# 08_BB_Processor.net
KiCad netlist of a schematic drawn in Altium Designer
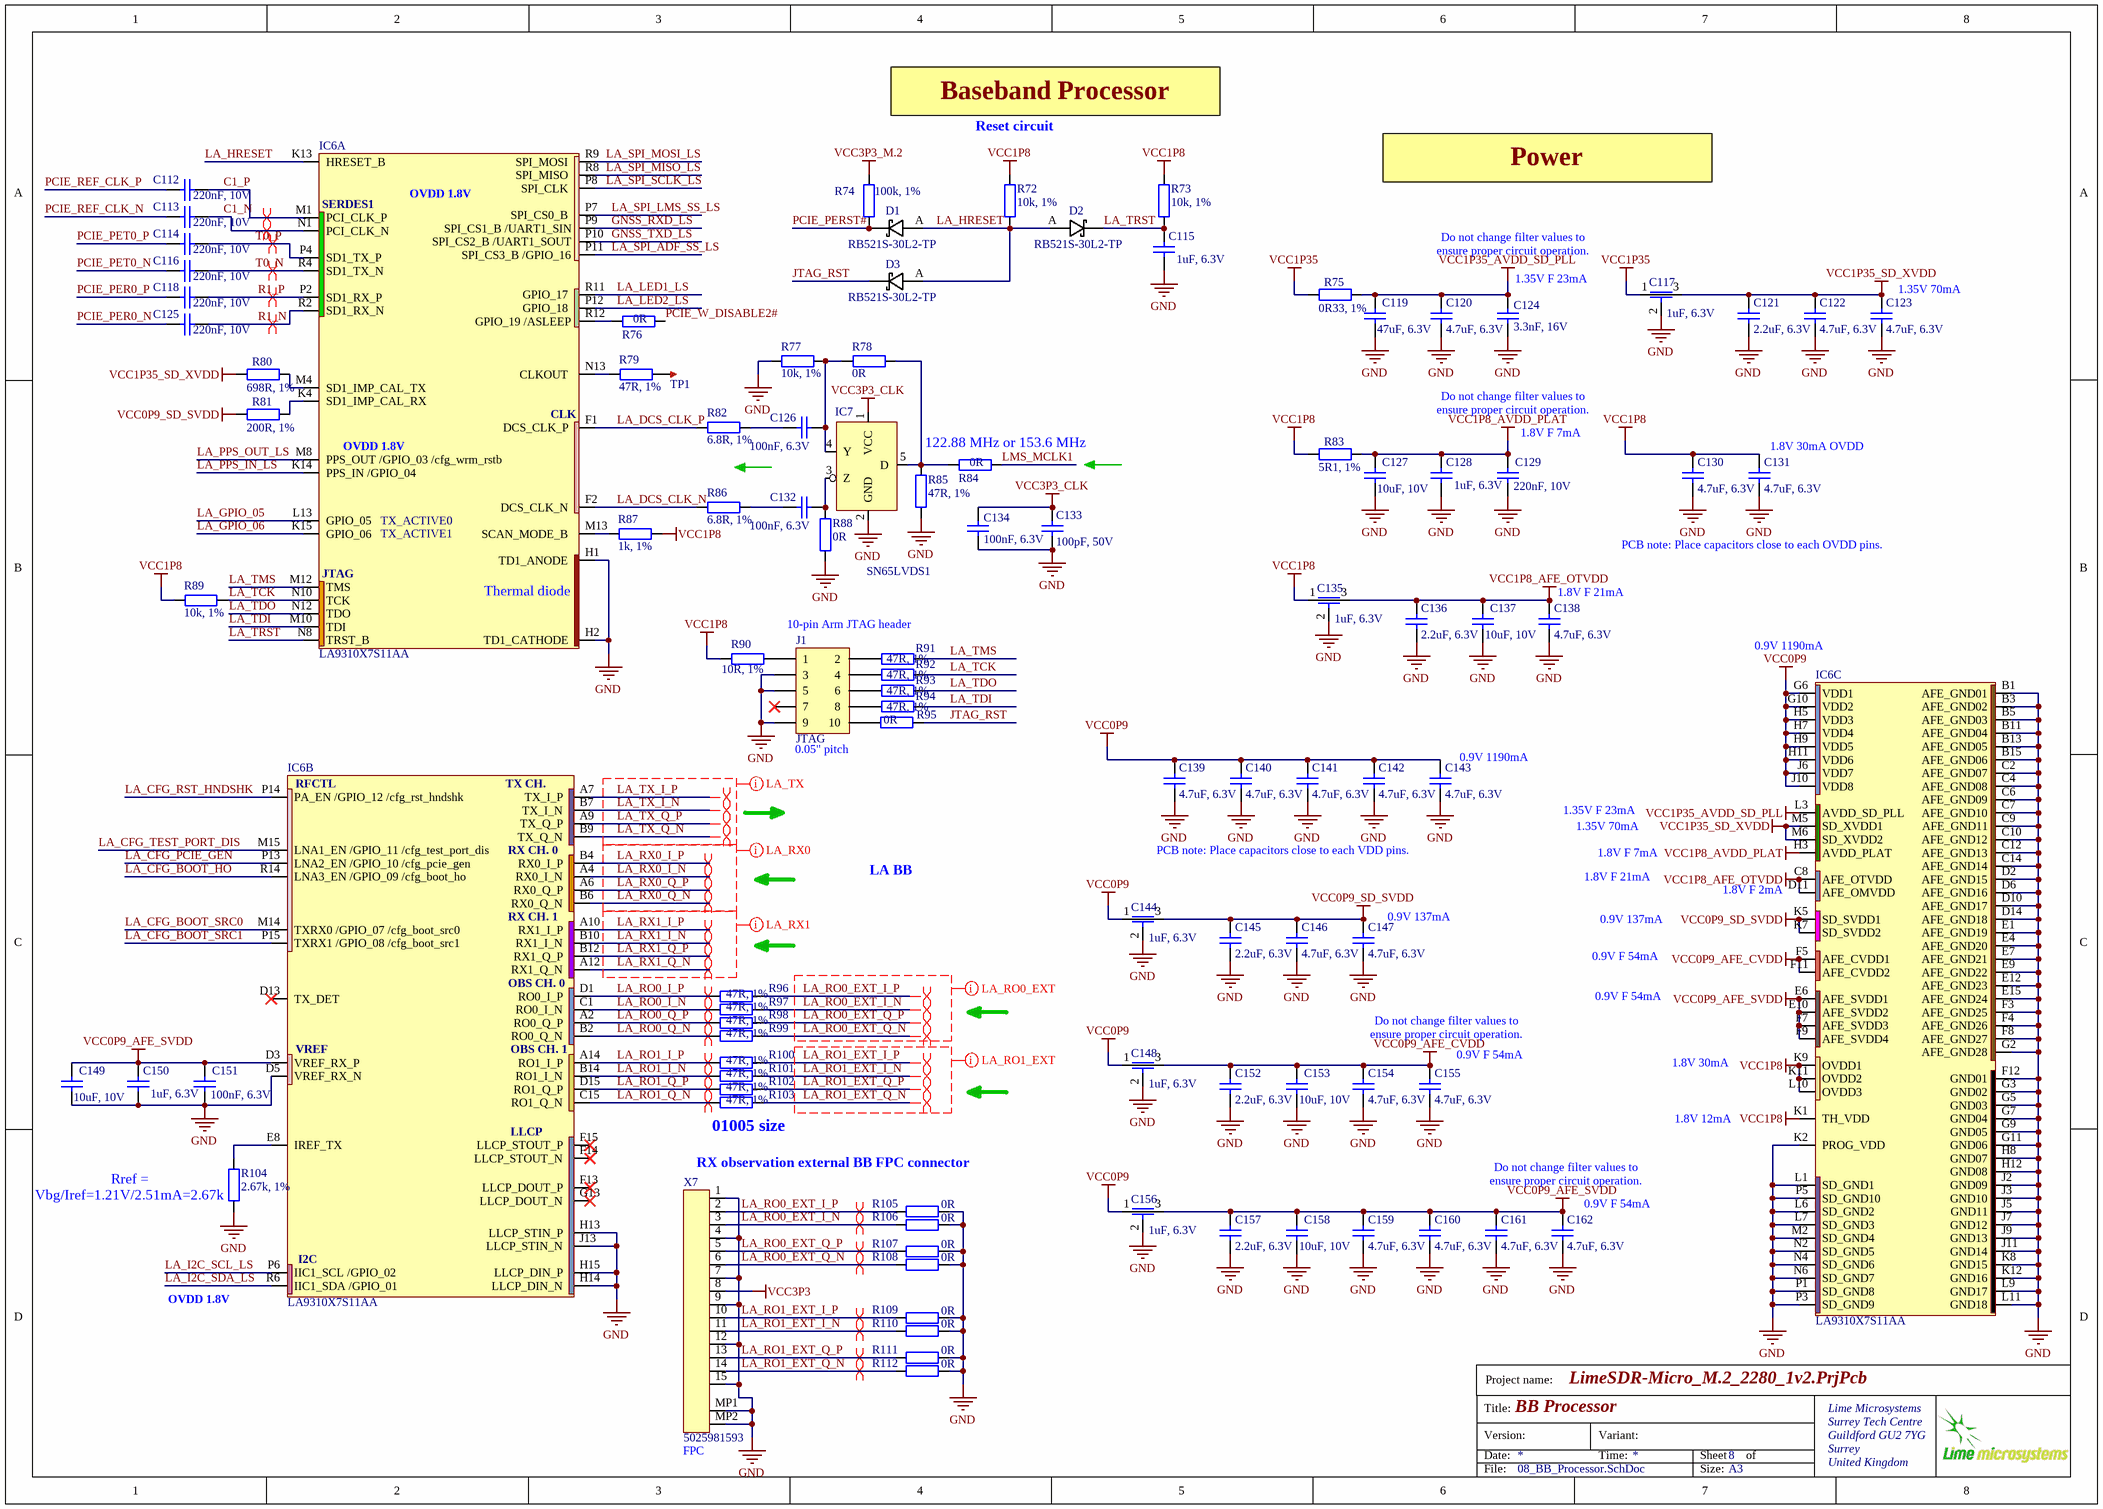
[diagram p0: 08_BB_Processor.SchDoc]

(export (version "E")
  (design (tool "Eeschema 10.0.6"))
  (components
    (comp (ref "C112")
      (value "220nF, 10V")
      (footprint "CAP0201")
      (fields
        (field (name "MANUFACTURER") "Murata")
        (field (name "TOLERANCE") "20%")
        (field (name "VOLTAGE") "10V")
      )
      (libsource (lib "LimeMicroAltiumLib_schLib") (part "Cap_0402"))
    )
    (comp (ref "C113")
      (value "220nF, 10V")
      (footprint "CAP0201")
      (fields
        (field (name "MANUFACTURER") "Murata")
        (field (name "TOLERANCE") "20%")
        (field (name "VOLTAGE") "10V")
      )
      (libsource (lib "LimeMicroAltiumLib_schLib") (part "Cap_0402"))
    )
    (comp (ref "C114")
      (value "220nF, 10V")
      (footprint "CAP0201")
      (fields
        (field (name "MANUFACTURER") "Murata")
        (field (name "TOLERANCE") "20%")
        (field (name "VOLTAGE") "10V")
      )
      (libsource (lib "LimeMicroAltiumLib_schLib") (part "Cap_0402"))
    )
    (comp (ref "C115")
      (value "1uF, 6.3V")
      (footprint "CAP0201")
      (fields (field (name "TOLERANCE") "±20%") (field (name "MANUFACTURER") "TDK Corporation"))
      (libsource (lib "LimeMicroAltiumLib_schLib") (part "Cap_0402"))
    )
    (comp (ref "C116")
      (value "220nF, 10V")
      (footprint "CAP0201")
      (fields
        (field (name "MANUFACTURER") "Murata")
        (field (name "TOLERANCE") "20%")
        (field (name "VOLTAGE") "10V")
      )
      (libsource (lib "LimeMicroAltiumLib_schLib") (part "Cap_0402"))
    )
    (comp (ref "C117")
      (value "1uF, 6.3V")
      (footprint "CAP0603_FEEDTHROUGH")
      (fields (field (name "MANUFACTURER") "TDK"))
      (libsource (lib "LimeMicroAltiumLib_schLib_r01") (part "Cap_feed_through"))
    )
    (comp (ref "C118")
      (value "220nF, 10V")
      (footprint "CAP0201")
      (fields
        (field (name "MANUFACTURER") "Murata")
        (field (name "TOLERANCE") "20%")
        (field (name "VOLTAGE") "10V")
      )
      (libsource (lib "LimeMicroAltiumLib_schLib") (part "Cap_0402"))
    )
    (comp (ref "C119")
      (value "47uF, 6.3V")
      (footprint "CAP0603")
      (fields (field (name "MANUFACTURER") "Murata") (field (name "TOLERANCE") "20%"))
      (libsource (lib "LimeFPGAboard_schLib") (part "Cap_0603"))
    )
    (comp (ref "C120")
      (value "4.7uF, 6.3V")
      (footprint "CAP0201")
      (fields (field (name "MANUFACTURER") "Murata") (field (name "TOLERANCE") "20%"))
      (libsource (lib "LimeMicroAltiumLib_schLib") (part "Cap_0402"))
    )
    (comp (ref "C121")
      (value "2.2uF, 6.3V")
      (footprint "CAP0201")
      (fields (field (name "MANUFACTURER") "Murata") (field (name "TOLERANCE") "20%"))
      (libsource (lib "LimeMicroAltiumLib_schLib") (part "Cap_0402"))
    )
    (comp (ref "C122")
      (value "4.7uF, 6.3V")
      (footprint "CAP0201")
      (fields (field (name "MANUFACTURER") "Murata") (field (name "TOLERANCE") "20%"))
      (libsource (lib "LimeMicroAltiumLib_schLib") (part "Cap_0402"))
    )
    (comp (ref "C123")
      (value "4.7uF, 6.3V")
      (footprint "CAP0201")
      (fields (field (name "MANUFACTURER") "Murata") (field (name "TOLERANCE") "20%"))
      (libsource (lib "LimeMicroAltiumLib_schLib") (part "Cap_0402"))
    )
    (comp (ref "C124")
      (value "3.3nF, 16V")
      (footprint "CAP0201")
      (fields (field (name "MANUFACTURER") "Murata"))
      (libsource (lib "LimeMicroAltiumLib_schLib") (part "Cap_0402"))
    )
    (comp (ref "C125")
      (value "220nF, 10V")
      (footprint "CAP0201")
      (fields
        (field (name "MANUFACTURER") "Murata")
        (field (name "TOLERANCE") "20%")
        (field (name "VOLTAGE") "10V")
      )
      (libsource (lib "LimeMicroAltiumLib_schLib") (part "Cap_0402"))
    )
    (comp (ref "C126")
      (value "100nF, 6.3V")
      (footprint "CAP0201")
      (fields (field (name "MANUFACTURER") "Samsung") (field (name "TOLERANCE") "20%"))
      (libsource (lib "LimeMicroAltiumLib_schLib") (part "Cap_0402"))
    )
    (comp (ref "C127")
      (value "10uF, 10V")
      (footprint "CAP0402")
      (fields (field (name "MANUFACTURER") "Murata"))
      (libsource (lib "LimeFPGAboard_schLib") (part "Cap_0603"))
    )
    (comp (ref "C128")
      (value "1uF, 6.3V")
      (footprint "CAP0201")
      (fields (field (name "TOLERANCE") "±20%") (field (name "MANUFACTURER") "TDK Corporation"))
      (libsource (lib "LimeMicroAltiumLib_schLib") (part "Cap_0402"))
    )
    (comp (ref "C129")
      (value "220nF, 10V")
      (footprint "CAP0201")
      (fields
        (field (name "MANUFACTURER") "Murata")
        (field (name "TOLERANCE") "20%")
        (field (name "VOLTAGE") "10V")
      )
      (libsource (lib "LimeMicroAltiumLib_schLib") (part "Cap_0402"))
    )
    (comp (ref "C130")
      (value "4.7uF, 6.3V")
      (footprint "CAP0201")
      (fields (field (name "MANUFACTURER") "Murata") (field (name "TOLERANCE") "20%"))
      (libsource (lib "LimeMicroAltiumLib_schLib") (part "Cap_0402"))
    )
    (comp (ref "C131")
      (value "4.7uF, 6.3V")
      (footprint "CAP0201")
      (fields (field (name "MANUFACTURER") "Murata") (field (name "TOLERANCE") "20%"))
      (libsource (lib "LimeMicroAltiumLib_schLib") (part "Cap_0402"))
    )
    (comp (ref "C132")
      (value "100nF, 6.3V")
      (footprint "CAP0201")
      (fields (field (name "MANUFACTURER") "Samsung") (field (name "TOLERANCE") "20%"))
      (libsource (lib "LimeMicroAltiumLib_schLib") (part "Cap_0402"))
    )
    (comp (ref "C133")
      (value "100pF, 50V")
      (footprint "CAP0201")
      (fields
        (field (name "MANUFACTURER") "TDK")
        (field (name "TOLERANCE") "5%")
        (field (name "VOLTAGE") "50V")
      )
      (libsource (lib "LimeMicroAltiumLib_schLib") (part "Cap_0402"))
    )
    (comp (ref "C134")
      (value "100nF, 6.3V")
      (footprint "CAP0201")
      (fields (field (name "MANUFACTURER") "Samsung") (field (name "TOLERANCE") "20%"))
      (libsource (lib "LimeMicroAltiumLib_schLib") (part "Cap_0402"))
    )
    (comp (ref "C135")
      (value "1uF, 6.3V")
      (footprint "CAP0603_FEEDTHROUGH")
      (fields (field (name "MANUFACTURER") "TDK"))
      (libsource (lib "LimeMicroAltiumLib_schLib_r01") (part "Cap_feed_through"))
    )
    (comp (ref "C136")
      (value "2.2uF, 6.3V")
      (footprint "CAP0201")
      (fields (field (name "MANUFACTURER") "Murata") (field (name "TOLERANCE") "20%"))
      (libsource (lib "LimeMicroAltiumLib_schLib") (part "Cap_0402"))
    )
    (comp (ref "C137")
      (value "10uF, 10V")
      (footprint "CAP0402")
      (fields (field (name "MANUFACTURER") "Murata"))
      (libsource (lib "LimeFPGAboard_schLib") (part "Cap_0603"))
    )
    (comp (ref "C138")
      (value "4.7uF, 6.3V")
      (footprint "CAP0201")
      (fields (field (name "MANUFACTURER") "Murata") (field (name "TOLERANCE") "20%"))
      (libsource (lib "LimeMicroAltiumLib_schLib") (part "Cap_0402"))
    )
    (comp (ref "C139")
      (value "4.7uF, 6.3V")
      (footprint "CAP0201")
      (fields (field (name "MANUFACTURER") "Murata") (field (name "TOLERANCE") "20%"))
      (libsource (lib "LimeMicroAltiumLib_schLib") (part "Cap_0402"))
    )
    (comp (ref "C140")
      (value "4.7uF, 6.3V")
      (footprint "CAP0201")
      (fields (field (name "MANUFACTURER") "Murata") (field (name "TOLERANCE") "20%"))
      (libsource (lib "LimeMicroAltiumLib_schLib") (part "Cap_0402"))
    )
    (comp (ref "C141")
      (value "4.7uF, 6.3V")
      (footprint "CAP0201")
      (fields (field (name "MANUFACTURER") "Murata") (field (name "TOLERANCE") "20%"))
      (libsource (lib "LimeMicroAltiumLib_schLib") (part "Cap_0402"))
    )
    (comp (ref "C142")
      (value "4.7uF, 6.3V")
      (footprint "CAP0201")
      (fields (field (name "MANUFACTURER") "Murata") (field (name "TOLERANCE") "20%"))
      (libsource (lib "LimeMicroAltiumLib_schLib") (part "Cap_0402"))
    )
    (comp (ref "C143")
      (value "4.7uF, 6.3V")
      (footprint "CAP0201")
      (fields (field (name "MANUFACTURER") "Murata") (field (name "TOLERANCE") "20%"))
      (libsource (lib "LimeMicroAltiumLib_schLib") (part "Cap_0402"))
    )
    (comp (ref "C144")
      (value "1uF, 6.3V")
      (footprint "CAP0603_FEEDTHROUGH")
      (fields (field (name "MANUFACTURER") "TDK"))
      (libsource (lib "LimeMicroAltiumLib_schLib_r01") (part "Cap_feed_through"))
    )
    (comp (ref "C145")
      (value "2.2uF, 6.3V")
      (footprint "CAP0201")
      (fields (field (name "MANUFACTURER") "Murata") (field (name "TOLERANCE") "20%"))
      (libsource (lib "LimeMicroAltiumLib_schLib") (part "Cap_0402"))
    )
    (comp (ref "C146")
      (value "4.7uF, 6.3V")
      (footprint "CAP0201")
      (fields (field (name "MANUFACTURER") "Murata") (field (name "TOLERANCE") "20%"))
      (libsource (lib "LimeMicroAltiumLib_schLib") (part "Cap_0402"))
    )
    (comp (ref "C147")
      (value "4.7uF, 6.3V")
      (footprint "CAP0201")
      (fields (field (name "MANUFACTURER") "Murata") (field (name "TOLERANCE") "20%"))
      (libsource (lib "LimeMicroAltiumLib_schLib") (part "Cap_0402"))
    )
    (comp (ref "C148")
      (value "1uF, 6.3V")
      (footprint "CAP0603_FEEDTHROUGH")
      (fields (field (name "MANUFACTURER") "TDK"))
      (libsource (lib "LimeMicroAltiumLib_schLib_r01") (part "Cap_feed_through"))
    )
    (comp (ref "C149")
      (value "10uF, 10V")
      (footprint "CAP0402")
      (fields (field (name "MANUFACTURER") "Murata"))
      (libsource (lib "LimeFPGAboard_schLib") (part "Cap_0603"))
    )
    (comp (ref "C150")
      (value "1uF, 6.3V")
      (footprint "CAP0201")
      (fields (field (name "TOLERANCE") "±20%") (field (name "MANUFACTURER") "TDK Corporation"))
      (libsource (lib "LimeMicroAltiumLib_schLib") (part "Cap_0402"))
    )
    (comp (ref "C151")
      (value "100nF, 6.3V")
      (footprint "CAP0201")
      (fields (field (name "MANUFACTURER") "Samsung") (field (name "TOLERANCE") "20%"))
      (libsource (lib "LimeMicroAltiumLib_schLib") (part "Cap_0402"))
    )
    (comp (ref "C152")
      (value "2.2uF, 6.3V")
      (footprint "CAP0201")
      (fields (field (name "MANUFACTURER") "Murata") (field (name "TOLERANCE") "20%"))
      (libsource (lib "LimeMicroAltiumLib_schLib") (part "Cap_0402"))
    )
    (comp (ref "C153")
      (value "10uF, 10V")
      (footprint "CAP0402")
      (fields (field (name "MANUFACTURER") "Murata"))
      (libsource (lib "LimeFPGAboard_schLib") (part "Cap_0603"))
    )
    (comp (ref "C154")
      (value "4.7uF, 6.3V")
      (footprint "CAP0201")
      (fields (field (name "MANUFACTURER") "Murata") (field (name "TOLERANCE") "20%"))
      (libsource (lib "LimeMicroAltiumLib_schLib") (part "Cap_0402"))
    )
    (comp (ref "C155")
      (value "4.7uF, 6.3V")
      (footprint "CAP0201")
      (fields (field (name "MANUFACTURER") "Murata") (field (name "TOLERANCE") "20%"))
      (libsource (lib "LimeMicroAltiumLib_schLib") (part "Cap_0402"))
    )
    (comp (ref "C156")
      (value "1uF, 6.3V")
      (footprint "CAP0603_FEEDTHROUGH")
      (fields (field (name "MANUFACTURER") "TDK"))
      (libsource (lib "LimeMicroAltiumLib_schLib_r01") (part "Cap_feed_through"))
    )
    (comp (ref "C157")
      (value "2.2uF, 6.3V")
      (footprint "CAP0201")
      (fields (field (name "MANUFACTURER") "Murata") (field (name "TOLERANCE") "20%"))
      (libsource (lib "LimeMicroAltiumLib_schLib") (part "Cap_0402"))
    )
    (comp (ref "C158")
      (value "10uF, 10V")
      (footprint "CAP0402")
      (fields (field (name "MANUFACTURER") "Murata"))
      (libsource (lib "LimeFPGAboard_schLib") (part "Cap_0603"))
    )
    (comp (ref "C159")
      (value "4.7uF, 6.3V")
      (footprint "CAP0201")
      (fields (field (name "MANUFACTURER") "Murata") (field (name "TOLERANCE") "20%"))
      (libsource (lib "LimeMicroAltiumLib_schLib") (part "Cap_0402"))
    )
    (comp (ref "C160")
      (value "4.7uF, 6.3V")
      (footprint "CAP0201")
      (fields (field (name "MANUFACTURER") "Murata") (field (name "TOLERANCE") "20%"))
      (libsource (lib "LimeMicroAltiumLib_schLib") (part "Cap_0402"))
    )
    (comp (ref "C161")
      (value "4.7uF, 6.3V")
      (footprint "CAP0201")
      (fields (field (name "MANUFACTURER") "Murata") (field (name "TOLERANCE") "20%"))
      (libsource (lib "LimeMicroAltiumLib_schLib") (part "Cap_0402"))
    )
    (comp (ref "C162")
      (value "4.7uF, 6.3V")
      (footprint "CAP0201")
      (fields (field (name "MANUFACTURER") "Murata") (field (name "TOLERANCE") "20%"))
      (libsource (lib "LimeMicroAltiumLib_schLib") (part "Cap_0402"))
    )
    (comp (ref "D1")
      (value "RB521S-30L2-TP")
      (footprint "RB521S-30L2-TP_DFN1006")
      (fields (field (name "MANUFACTURER") "MCC"))
      (libsource (lib "LimeMicroAltiumLib") (part "BAT46JFILM_shottky_diode"))
    )
    (comp (ref "D2")
      (value "RB521S-30L2-TP")
      (footprint "RB521S-30L2-TP_DFN1006")
      (fields (field (name "MANUFACTURER") "MCC"))
      (libsource (lib "LimeMicroAltiumLib") (part "BAT46JFILM_shottky_diode"))
    )
    (comp (ref "D3")
      (value "RB521S-30L2-TP")
      (footprint "RB521S-30L2-TP_DFN1006")
      (fields (field (name "MANUFACTURER") "MCC"))
      (libsource (lib "LimeMicroAltiumLib") (part "BAT46JFILM_shottky_diode"))
    )
    (comp (ref "IC6")
      (value "LA9310X7S11AA")
      (footprint "LA9310X7S11AA")
      (fields (field (name "MANUFACTURER") "NXP Semiconductors"))
      (libsource (lib "LimeMicroAltiumLib") (part "LA9310X7S11AA"))
    )
    (comp (ref "IC7")
      (value "SN65LVDS1")
      (footprint "SOT23-5_NO_SILK")
      (fields (field (name "MANUFACTURER") "TEXAS INSTRUMENTS"))
      (libsource (lib "LimeMicroAltiumLib_schLib") (part "SN65LVDS1"))
    )
    (comp (ref "J1")
      (value "JTAG")
      (footprint "HEADER_5x2_TH_HALF_PITCH")
      (description "Header, 5-Pin, Dual row")
      (fields (field (name "MANUFACTURER") "Adam Equipment"))
      (libsource (lib "LimeMicroAltiumLib") (part "Header 5X2_SWD"))
    )
    (comp (ref "R72")
      (value "10k, 1%")
      (footprint "RES0201")
      (fields (field (name "MANUFACTURER") "Yageo") (field (name "TOLERANCE") "1%"))
      (libsource (lib "LimeFPGAboard_schLib") (part "Res_0402"))
    )
    (comp (ref "R73")
      (value "10k, 1%")
      (footprint "RES0201")
      (fields (field (name "MANUFACTURER") "Yageo") (field (name "TOLERANCE") "1%"))
      (libsource (lib "LimeFPGAboard_schLib") (part "Res_0402"))
    )
    (comp (ref "R74")
      (value "100k, 1%")
      (footprint "RES0201")
      (fields (field (name "MANUFACTURER") "Yageo") (field (name "TOLERANCE") "1%"))
      (libsource (lib "LimeFPGAboard_schLib") (part "Res_0402"))
    )
    (comp (ref "R75")
      (value "0R33, 1%")
      (footprint "RES0201")
      (fields (field (name "MANUFACTURER") "Ohmite"))
      (libsource (lib "LimeFPGAboard_schLib") (part "Res_0402"))
    )
    (comp (ref "R76")
      (value "0R")
      (footprint "RES0201")
      (fields (field (name "MANUFACTURER") "Yageo") (field (name "TOLERANCE") "5%"))
      (libsource (lib "LimeFPGAboard_schLib") (part "Res_0402"))
    )
    (comp (ref "R77")
      (value "10k, 1%")
      (footprint "RES0201")
      (fields (field (name "MANUFACTURER") "Yageo") (field (name "TOLERANCE") "1%"))
      (libsource (lib "LimeFPGAboard_schLib") (part "Res_0402"))
    )
    (comp (ref "R78")
      (value "0R")
      (footprint "RES0201")
      (fields (field (name "MANUFACTURER") "Yageo") (field (name "TOLERANCE") "5%"))
      (libsource (lib "LimeFPGAboard_schLib") (part "Res_0402"))
    )
    (comp (ref "R79")
      (value "47R, 1%")
      (footprint "RES0201")
      (fields (field (name "MANUFACTURER") "Yageo") (field (name "TOLERANCE") "1%"))
      (libsource (lib "LimeFPGAboard_schLib") (part "Res_0402"))
    )
    (comp (ref "R80")
      (value "698R, 1%")
      (footprint "RES0201")
      (fields (field (name "MANUFACTURER") "Yageo") (field (name "TOLERANCE") "1%"))
      (libsource (lib "LimeFPGAboard_schLib") (part "Res_0402"))
    )
    (comp (ref "R81")
      (value "200R, 1%")
      (footprint "RES0201")
      (fields (field (name "MANUFACTURER") "Yageo") (field (name "TOLERANCE") "1%"))
      (libsource (lib "LimeFPGAboard_schLib") (part "Res_0402"))
    )
    (comp (ref "R82")
      (value "6.8R, 1%")
      (footprint "RES0201")
      (fields (field (name "MANUFACTURER") "Yageo") (field (name "TOLERANCE") "1%"))
      (libsource (lib "LimeMicroAltiumLib_schLib") (part "Res_0402"))
    )
    (comp (ref "R83")
      (value "5R1, 1%")
      (footprint "RES0201")
      (fields (field (name "MANUFACTURER") "Yageo"))
      (libsource (lib "LimeFPGAboard_schLib") (part "Res_0402"))
    )
    (comp (ref "R84")
      (value "0R")
      (footprint "RES0201")
      (fields (field (name "MANUFACTURER") "Yageo") (field (name "TOLERANCE") "5%"))
      (libsource (lib "LimeFPGAboard_schLib") (part "Res_0402"))
    )
    (comp (ref "R85")
      (value "47R, 1%")
      (footprint "RES0201")
      (fields (field (name "MANUFACTURER") "Yageo") (field (name "TOLERANCE") "1%"))
      (libsource (lib "LimeFPGAboard_schLib") (part "Res_0402"))
    )
    (comp (ref "R86")
      (value "6.8R, 1%")
      (footprint "RES0201")
      (fields (field (name "MANUFACTURER") "Yageo") (field (name "TOLERANCE") "1%"))
      (libsource (lib "LimeMicroAltiumLib_schLib") (part "Res_0402"))
    )
    (comp (ref "R87")
      (value "1k, 1%")
      (footprint "RES0201")
      (fields (field (name "MANUFACTURER") "Yageo") (field (name "TOLERANCE") "1%"))
      (libsource (lib "LimeMicroAltiumLib_schLib") (part "Res_0402"))
    )
    (comp (ref "R88")
      (value "0R")
      (footprint "RES0201")
      (fields (field (name "MANUFACTURER") "Yageo") (field (name "TOLERANCE") "5%"))
      (libsource (lib "LimeFPGAboard_schLib") (part "Res_0402"))
    )
    (comp (ref "R89")
      (value "10k, 1%")
      (footprint "RES0201")
      (fields (field (name "MANUFACTURER") "Yageo") (field (name "TOLERANCE") "1%"))
      (libsource (lib "LimeFPGAboard_schLib") (part "Res_0402"))
    )
    (comp (ref "R90")
      (value "10R, 1%")
      (footprint "RES0201")
      (fields
        (field (name "MANUFACTURER") "Panasonic Electronic Components")
        (field (name "TOLERANCE") "±1%")
      )
      (libsource (lib "LimeMicroAltiumLib_schLib") (part "Res_0402"))
    )
    (comp (ref "R91")
      (value "47R, 1%")
      (footprint "RES0201")
      (fields (field (name "MANUFACTURER") "Yageo") (field (name "TOLERANCE") "1%"))
      (libsource (lib "LimeFPGAboard_schLib") (part "Res_0402"))
    )
    (comp (ref "R92")
      (value "47R, 1%")
      (footprint "RES0201")
      (fields (field (name "MANUFACTURER") "Yageo") (field (name "TOLERANCE") "1%"))
      (libsource (lib "LimeFPGAboard_schLib") (part "Res_0402"))
    )
    (comp (ref "R93")
      (value "47R, 1%")
      (footprint "RES0201")
      (fields (field (name "MANUFACTURER") "Yageo") (field (name "TOLERANCE") "1%"))
      (libsource (lib "LimeFPGAboard_schLib") (part "Res_0402"))
    )
    (comp (ref "R94")
      (value "47R, 1%")
      (footprint "RES0201")
      (fields (field (name "MANUFACTURER") "Yageo") (field (name "TOLERANCE") "1%"))
      (libsource (lib "LimeFPGAboard_schLib") (part "Res_0402"))
    )
    (comp (ref "R95")
      (value "0R")
      (footprint "RES0201")
      (fields (field (name "MANUFACTURER") "Yageo") (field (name "TOLERANCE") "5%"))
      (libsource (lib "LimeFPGAboard_schLib") (part "Res_0402"))
    )
    (comp (ref "R96")
      (value "47R, 1%")
      (footprint "RES01005")
      (fields (field (name "MANUFACTURER") "Yageo") (field (name "TOLERANCE") "1%"))
      (libsource (lib "LimeFPGAboard_schLib") (part "Res_0402"))
    )
    (comp (ref "R97")
      (value "47R, 1%")
      (footprint "RES01005")
      (fields (field (name "MANUFACTURER") "Yageo") (field (name "TOLERANCE") "1%"))
      (libsource (lib "LimeFPGAboard_schLib") (part "Res_0402"))
    )
    (comp (ref "R98")
      (value "47R, 1%")
      (footprint "RES01005")
      (fields (field (name "MANUFACTURER") "Yageo") (field (name "TOLERANCE") "1%"))
      (libsource (lib "LimeFPGAboard_schLib") (part "Res_0402"))
    )
    (comp (ref "R99")
      (value "47R, 1%")
      (footprint "RES01005")
      (fields (field (name "MANUFACTURER") "Yageo") (field (name "TOLERANCE") "1%"))
      (libsource (lib "LimeFPGAboard_schLib") (part "Res_0402"))
    )
    (comp (ref "R100")
      (value "47R, 1%")
      (footprint "RES01005")
      (fields (field (name "MANUFACTURER") "Yageo") (field (name "TOLERANCE") "1%"))
      (libsource (lib "LimeFPGAboard_schLib") (part "Res_0402"))
    )
    (comp (ref "R101")
      (value "47R, 1%")
      (footprint "RES01005")
      (fields (field (name "MANUFACTURER") "Yageo") (field (name "TOLERANCE") "1%"))
      (libsource (lib "LimeFPGAboard_schLib") (part "Res_0402"))
    )
    (comp (ref "R102")
      (value "47R, 1%")
      (footprint "RES01005")
      (fields (field (name "MANUFACTURER") "Yageo") (field (name "TOLERANCE") "1%"))
      (libsource (lib "LimeFPGAboard_schLib") (part "Res_0402"))
    )
    (comp (ref "R103")
      (value "47R, 1%")
      (footprint "RES01005")
      (fields (field (name "MANUFACTURER") "Yageo") (field (name "TOLERANCE") "1%"))
      (libsource (lib "LimeFPGAboard_schLib") (part "Res_0402"))
    )
    (comp (ref "R104")
      (value "2.67k, 1%")
      (footprint "RES0201")
      (fields (field (name "MANUFACTURER") "Stackpole Electronics") (field (name "TOLERANCE") "1%"))
      (libsource (lib "LimeFPGAboard_schLib") (part "Res_0402"))
    )
    (comp (ref "R105")
      (value "0R")
      (footprint "RES01005")
      (fields (field (name "MANUFACTURER") "Panasonic") (field (name "TOLERANCE") "5%"))
      (libsource (lib "LimeFPGAboard_schLib") (part "Res_0402"))
    )
    (comp (ref "R106")
      (value "0R")
      (footprint "RES01005")
      (fields (field (name "MANUFACTURER") "Panasonic") (field (name "TOLERANCE") "5%"))
      (libsource (lib "LimeFPGAboard_schLib") (part "Res_0402"))
    )
    (comp (ref "R107")
      (value "0R")
      (footprint "RES01005")
      (fields (field (name "MANUFACTURER") "Panasonic") (field (name "TOLERANCE") "5%"))
      (libsource (lib "LimeFPGAboard_schLib") (part "Res_0402"))
    )
    (comp (ref "R108")
      (value "0R")
      (footprint "RES01005")
      (fields (field (name "MANUFACTURER") "Panasonic") (field (name "TOLERANCE") "5%"))
      (libsource (lib "LimeFPGAboard_schLib") (part "Res_0402"))
    )
    (comp (ref "R109")
      (value "0R")
      (footprint "RES01005")
      (fields (field (name "MANUFACTURER") "Panasonic") (field (name "TOLERANCE") "5%"))
      (libsource (lib "LimeFPGAboard_schLib") (part "Res_0402"))
    )
    (comp (ref "R110")
      (value "0R")
      (footprint "RES01005")
      (fields (field (name "MANUFACTURER") "Panasonic") (field (name "TOLERANCE") "5%"))
      (libsource (lib "LimeFPGAboard_schLib") (part "Res_0402"))
    )
    (comp (ref "R111")
      (value "0R")
      (footprint "RES01005")
      (fields (field (name "MANUFACTURER") "Panasonic") (field (name "TOLERANCE") "5%"))
      (libsource (lib "LimeFPGAboard_schLib") (part "Res_0402"))
    )
    (comp (ref "R112")
      (value "0R")
      (footprint "RES01005")
      (fields (field (name "MANUFACTURER") "Panasonic") (field (name "TOLERANCE") "5%"))
      (libsource (lib "LimeFPGAboard_schLib") (part "Res_0402"))
    )
    (comp (ref "TP1")
      (value "TESTPOINT_PAD")
      (footprint "TP_PAD_1MM")
      (description "Test Point PCB mount Miniature White")
      (libsource (lib "LimeMicroAltiumLib_schLib_r04") (part "TESTPOINT_PAD"))
    )
    (comp (ref "X7")
      (value "5025981593")
      (footprint "5025981593_FPC_connector")
      (fields (field (name "MANUFACTURER") "Molex"))
      (libsource (lib "LimeMicroAltiumLib_schLib_r04") (part "5025981593_FPC_connector"))
    )
  )
  (nets
    (net (code "1") (name "/C1_N") (class "Default")
      (node (ref "C113") (pin "2") (pinfunction "2_2") (pintype "passive"))
      (node (ref "IC6") (pin "N1") (pinfunction "PCI_CLK_N_N1") (pintype "power_in"))
    )
    (net (code "2") (name "/C1_P") (class "Default")
      (node (ref "C112") (pin "2") (pinfunction "2_2") (pintype "passive"))
      (node (ref "IC6") (pin "M1") (pinfunction "PCI_CLK_P_M1") (pintype "power_in"))
    )
    (net (code "3") (name "/GNSS_RXD_LS") (class "Default")
      (node (ref "IC6") (pin "P9") (pinfunction "SPI_CS1_B_/UART1_SIN_P9") (pintype "power_in"))
    )
    (net (code "4") (name "/GNSS_TXD_LS") (class "Default")
      (node (ref "IC6") (pin "P10") (pinfunction "SPI_CS2_B_/UART1_SOUT_P10") (pintype "power_in"))
    )
    (net (code "5") (name "/JTAG_RST") (class "Default")
      (node (ref "D3") (pin "C") (pinfunction "C_C") (pintype "passive"))
      (node (ref "R95") (pin "2") (pinfunction "2_2") (pintype "passive"))
    )
    (net (code "6") (name "/LA_CFG_BOOT_HO") (class "Default")
      (node (ref "IC6") (pin "R14") (pinfunction "LNA3_EN_/GPIO_09_/cfg_boot_ho_R14") (pintype "power_in"))
    )
    (net (code "7") (name "/LA_CFG_BOOT_SRC0") (class "Default")
      (node (ref "IC6") (pin "M14") (pinfunction "TXRX0_/GPIO_07_/cfg_boot_src0_M14") (pintype "power_in"))
    )
    (net (code "8") (name "/LA_CFG_BOOT_SRC1") (class "Default")
      (node (ref "IC6") (pin "P15") (pinfunction "TXRX1_/GPIO_08_/cfg_boot_src1_P15") (pintype "power_in"))
    )
    (net (code "9") (name "/LA_CFG_PCIE_GEN") (class "Default")
      (node (ref "IC6") (pin "P13") (pinfunction "LNA2_EN_/GPIO_10_/cfg_pcie_gen_P13") (pintype "power_in"))
    )
    (net (code "10") (name "/LA_CFG_RST_HNDSHK") (class "Default")
      (node (ref "IC6") (pin "P14") (pinfunction "PA_EN_/GPIO_12_/cfg_rst_hndshk_P14") (pintype "power_in"))
    )
    (net (code "11") (name "/LA_CFG_TEST_PORT_DIS") (class "Default")
      (node (ref "IC6") (pin "M15") (pinfunction "LNA1_EN_/GPIO_11_/cfg_test_port_dis_M15") (pintype "power_in"))
    )
    (net (code "12") (name "/LA_DCS_CLK_N") (class "Default")
      (node (ref "IC6") (pin "F2") (pinfunction "DCS_CLK_N_F2") (pintype "power_in"))
      (node (ref "R86") (pin "2") (pinfunction "2_2") (pintype "passive"))
    )
    (net (code "13") (name "/LA_DCS_CLK_P") (class "Default")
      (node (ref "IC6") (pin "F1") (pinfunction "DCS_CLK_P_F1") (pintype "power_in"))
      (node (ref "R82") (pin "2") (pinfunction "2_2") (pintype "passive"))
    )
    (net (code "14") (name "/LA_GPIO_05") (class "Default")
      (node (ref "IC6") (pin "L13") (pinfunction "GPIO_05_L13") (pintype "power_in"))
    )
    (net (code "15") (name "/LA_GPIO_06") (class "Default")
      (node (ref "IC6") (pin "K15") (pinfunction "GPIO_06_K15") (pintype "power_in"))
    )
    (net (code "16") (name "/LA_HRESET") (class "Default")
      (node (ref "D1") (pin "A") (pinfunction "A_A") (pintype "passive"))
      (node (ref "D2") (pin "A") (pinfunction "A_A") (pintype "passive"))
      (node (ref "D3") (pin "A") (pinfunction "A_A") (pintype "passive"))
      (node (ref "IC6") (pin "K13") (pinfunction "HRESET_B_K13") (pintype "power_in"))
      (node (ref "R72") (pin "2") (pinfunction "2_2") (pintype "passive"))
    )
    (net (code "17") (name "/LA_I2C_SCL_LS") (class "Default")
      (node (ref "IC6") (pin "P6") (pinfunction "IIC1_SCL_/GPIO_02_P6") (pintype "power_in"))
    )
    (net (code "18") (name "/LA_I2C_SDA_LS") (class "Default")
      (node (ref "IC6") (pin "R6") (pinfunction "IIC1_SDA_/GPIO_01_R6") (pintype "power_in"))
    )
    (net (code "19") (name "/LA_LED1_LS") (class "Default")
      (node (ref "IC6") (pin "R11") (pinfunction "GPIO_17_R11") (pintype "power_in"))
    )
    (net (code "20") (name "/LA_LED2_LS") (class "Default")
      (node (ref "IC6") (pin "P12") (pinfunction "GPIO_18_P12") (pintype "power_in"))
    )
    (net (code "21") (name "/LA_PPS_IN_LS") (class "Default")
      (node (ref "IC6") (pin "K14") (pinfunction "PPS_IN_/GPIO_04_K14") (pintype "power_in"))
    )
    (net (code "22") (name "/LA_PPS_OUT_LS") (class "Default")
      (node (ref "IC6") (pin "M8") (pinfunction "PPS_OUT_/GPIO_03_/cfg_wrm_rstb_M8") (pintype "power_in"))
    )
    (net (code "23") (name "/LA_RO0_EXT_I_N") (class "Default")
      (node (ref "R106") (pin "1") (pinfunction "1_1") (pintype "passive"))
      (node (ref "R97") (pin "2") (pinfunction "2_2") (pintype "passive"))
      (node (ref "X7") (pin "3") (pinfunction "3_3") (pintype "passive"))
    )
    (net (code "24") (name "/LA_RO0_EXT_I_P") (class "Default")
      (node (ref "R105") (pin "1") (pinfunction "1_1") (pintype "passive"))
      (node (ref "R96") (pin "2") (pinfunction "2_2") (pintype "passive"))
      (node (ref "X7") (pin "2") (pinfunction "2_2") (pintype "passive"))
    )
    (net (code "25") (name "/LA_RO0_EXT_Q_N") (class "Default")
      (node (ref "R108") (pin "1") (pinfunction "1_1") (pintype "passive"))
      (node (ref "R99") (pin "2") (pinfunction "2_2") (pintype "passive"))
      (node (ref "X7") (pin "6") (pinfunction "6_6") (pintype "passive"))
    )
    (net (code "26") (name "/LA_RO0_EXT_Q_P") (class "Default")
      (node (ref "R107") (pin "1") (pinfunction "1_1") (pintype "passive"))
      (node (ref "R98") (pin "2") (pinfunction "2_2") (pintype "passive"))
      (node (ref "X7") (pin "5") (pinfunction "5_5") (pintype "passive"))
    )
    (net (code "27") (name "/LA_RO0_I_N") (class "Default")
      (node (ref "IC6") (pin "C1") (pinfunction "RO0_I_N_C1") (pintype "power_in"))
      (node (ref "R97") (pin "1") (pinfunction "1_1") (pintype "passive"))
    )
    (net (code "28") (name "/LA_RO0_I_P") (class "Default")
      (node (ref "IC6") (pin "D1") (pinfunction "RO0_I_P_D1") (pintype "power_in"))
      (node (ref "R96") (pin "1") (pinfunction "1_1") (pintype "passive"))
    )
    (net (code "29") (name "/LA_RO0_Q_N") (class "Default")
      (node (ref "IC6") (pin "B2") (pinfunction "RO0_Q_N_B2") (pintype "power_in"))
      (node (ref "R99") (pin "1") (pinfunction "1_1") (pintype "passive"))
    )
    (net (code "30") (name "/LA_RO0_Q_P") (class "Default")
      (node (ref "IC6") (pin "A2") (pinfunction "RO0_Q_P_A2") (pintype "power_in"))
      (node (ref "R98") (pin "1") (pinfunction "1_1") (pintype "passive"))
    )
    (net (code "31") (name "/LA_RO1_EXT_I_N") (class "Default")
      (node (ref "R101") (pin "2") (pinfunction "2_2") (pintype "passive"))
      (node (ref "R110") (pin "1") (pinfunction "1_1") (pintype "passive"))
      (node (ref "X7") (pin "11") (pinfunction "11_11") (pintype "passive"))
    )
    (net (code "32") (name "/LA_RO1_EXT_I_P") (class "Default")
      (node (ref "R100") (pin "2") (pinfunction "2_2") (pintype "passive"))
      (node (ref "R109") (pin "1") (pinfunction "1_1") (pintype "passive"))
      (node (ref "X7") (pin "10") (pinfunction "10_10") (pintype "passive"))
    )
    (net (code "33") (name "/LA_RO1_EXT_Q_N") (class "Default")
      (node (ref "R103") (pin "2") (pinfunction "2_2") (pintype "passive"))
      (node (ref "R112") (pin "1") (pinfunction "1_1") (pintype "passive"))
      (node (ref "X7") (pin "14") (pinfunction "14_14") (pintype "passive"))
    )
    (net (code "34") (name "/LA_RO1_EXT_Q_P") (class "Default")
      (node (ref "R102") (pin "2") (pinfunction "2_2") (pintype "passive"))
      (node (ref "R111") (pin "1") (pinfunction "1_1") (pintype "passive"))
      (node (ref "X7") (pin "13") (pinfunction "13_13") (pintype "passive"))
    )
    (net (code "35") (name "/LA_RO1_I_N") (class "Default")
      (node (ref "IC6") (pin "B14") (pinfunction "RO1_I_N_B14") (pintype "power_in"))
      (node (ref "R101") (pin "1") (pinfunction "1_1") (pintype "passive"))
    )
    (net (code "36") (name "/LA_RO1_I_P") (class "Default")
      (node (ref "IC6") (pin "A14") (pinfunction "RO1_I_P_A14") (pintype "power_in"))
      (node (ref "R100") (pin "1") (pinfunction "1_1") (pintype "passive"))
    )
    (net (code "37") (name "/LA_RO1_Q_N") (class "Default")
      (node (ref "IC6") (pin "C15") (pinfunction "RO1_Q_N_C15") (pintype "power_in"))
      (node (ref "R103") (pin "1") (pinfunction "1_1") (pintype "passive"))
    )
    (net (code "38") (name "/LA_RO1_Q_P") (class "Default")
      (node (ref "IC6") (pin "D15") (pinfunction "RO1_Q_P_D15") (pintype "power_in"))
      (node (ref "R102") (pin "1") (pinfunction "1_1") (pintype "passive"))
    )
    (net (code "39") (name "/LA_RX0_I_N") (class "Default")
      (node (ref "IC6") (pin "A4") (pinfunction "RX0_I_N_A4") (pintype "power_in"))
    )
    (net (code "40") (name "/LA_RX0_I_P") (class "Default")
      (node (ref "IC6") (pin "B4") (pinfunction "RX0_I_P_B4") (pintype "power_in"))
    )
    (net (code "41") (name "/LA_RX0_Q_N") (class "Default")
      (node (ref "IC6") (pin "B6") (pinfunction "RX0_Q_N_B6") (pintype "power_in"))
    )
    (net (code "42") (name "/LA_RX0_Q_P") (class "Default")
      (node (ref "IC6") (pin "A6") (pinfunction "RX0_Q_P_A6") (pintype "power_in"))
    )
    (net (code "43") (name "/LA_RX1_I_N") (class "Default")
      (node (ref "IC6") (pin "B10") (pinfunction "RX1_I_N_B10") (pintype "power_in"))
    )
    (net (code "44") (name "/LA_RX1_I_P") (class "Default")
      (node (ref "IC6") (pin "A10") (pinfunction "RX1_I_P_A10") (pintype "power_in"))
    )
    (net (code "45") (name "/LA_RX1_Q_N") (class "Default")
      (node (ref "IC6") (pin "A12") (pinfunction "RX1_Q_N_A12") (pintype "power_in"))
    )
    (net (code "46") (name "/LA_RX1_Q_P") (class "Default")
      (node (ref "IC6") (pin "B12") (pinfunction "RX1_Q_P_B12") (pintype "power_in"))
    )
    (net (code "47") (name "/LA_SPI_ADF_SS_LS") (class "Default")
      (node (ref "IC6") (pin "P11") (pinfunction "SPI_CS3_B_/GPIO_16_P11") (pintype "power_in"))
    )
    (net (code "48") (name "/LA_SPI_LMS_SS_LS") (class "Default")
      (node (ref "IC6") (pin "P7") (pinfunction "SPI_CS0_B_P7") (pintype "power_in"))
    )
    (net (code "49") (name "/LA_SPI_MISO_LS") (class "Default")
      (node (ref "IC6") (pin "R8") (pinfunction "SPI_MISO_R8") (pintype "power_in"))
    )
    (net (code "50") (name "/LA_SPI_MOSI_LS") (class "Default")
      (node (ref "IC6") (pin "R9") (pinfunction "SPI_MOSI_R9") (pintype "power_in"))
    )
    (net (code "51") (name "/LA_SPI_SCLK_LS") (class "Default")
      (node (ref "IC6") (pin "P8") (pinfunction "SPI_CLK_P8") (pintype "power_in"))
    )
    (net (code "52") (name "/LA_TCK") (class "Default")
      (node (ref "IC6") (pin "N10") (pinfunction "TCK_N10") (pintype "power_in"))
      (node (ref "R89") (pin "2") (pinfunction "2_2") (pintype "passive"))
      (node (ref "R92") (pin "1") (pinfunction "1_1") (pintype "passive"))
    )
    (net (code "53") (name "/LA_TDI") (class "Default")
      (node (ref "IC6") (pin "M10") (pinfunction "TDI_M10") (pintype "power_in"))
      (node (ref "R94") (pin "1") (pinfunction "1_1") (pintype "passive"))
    )
    (net (code "54") (name "/LA_TDO") (class "Default")
      (node (ref "IC6") (pin "N12") (pinfunction "TDO_N12") (pintype "power_in"))
      (node (ref "R93") (pin "1") (pinfunction "1_1") (pintype "passive"))
    )
    (net (code "55") (name "/LA_TMS") (class "Default")
      (node (ref "IC6") (pin "M12") (pinfunction "TMS_M12") (pintype "power_in"))
      (node (ref "R91") (pin "1") (pinfunction "1_1") (pintype "passive"))
    )
    (net (code "56") (name "/LA_TRST") (class "Default")
      (node (ref "C115") (pin "1") (pinfunction "1_1") (pintype "passive"))
      (node (ref "D2") (pin "C") (pinfunction "C_C") (pintype "passive"))
      (node (ref "IC6") (pin "N8") (pinfunction "TRST_B_N8") (pintype "power_in"))
      (node (ref "R73") (pin "2") (pinfunction "2_2") (pintype "passive"))
    )
    (net (code "57") (name "/LA_TX_I_N") (class "Default")
      (node (ref "IC6") (pin "B7") (pinfunction "TX_I_N_B7") (pintype "power_in"))
    )
    (net (code "58") (name "/LA_TX_I_P") (class "Default")
      (node (ref "IC6") (pin "A7") (pinfunction "TX_I_P_A7") (pintype "power_in"))
    )
    (net (code "59") (name "/LA_TX_Q_N") (class "Default")
      (node (ref "IC6") (pin "B9") (pinfunction "TX_Q_N_B9") (pintype "power_in"))
    )
    (net (code "60") (name "/LA_TX_Q_P") (class "Default")
      (node (ref "IC6") (pin "A9") (pinfunction "TX_Q_P_A9") (pintype "power_in"))
    )
    (net (code "61") (name "/LMS_MCLK1") (class "Default")
      (node (ref "R84") (pin "1") (pinfunction "1_1") (pintype "passive"))
    )
    (net (code "62") (name "/PCIE_PER0_N") (class "Default")
      (node (ref "C125") (pin "1") (pinfunction "1_1") (pintype "passive"))
    )
    (net (code "63") (name "/PCIE_PER0_P") (class "Default")
      (node (ref "C118") (pin "1") (pinfunction "1_1") (pintype "passive"))
    )
    (net (code "64") (name "/PCIE_PERST#") (class "Default")
      (node (ref "D1") (pin "C") (pinfunction "C_C") (pintype "passive"))
      (node (ref "R74") (pin "2") (pinfunction "2_2") (pintype "passive"))
    )
    (net (code "65") (name "/PCIE_PET0_N") (class "Default")
      (node (ref "C116") (pin "1") (pinfunction "1_1") (pintype "passive"))
    )
    (net (code "66") (name "/PCIE_PET0_P") (class "Default")
      (node (ref "C114") (pin "1") (pinfunction "1_1") (pintype "passive"))
    )
    (net (code "67") (name "/PCIE_REF_CLK_N") (class "Default")
      (node (ref "C113") (pin "1") (pinfunction "1_1") (pintype "passive"))
    )
    (net (code "68") (name "/PCIE_REF_CLK_P") (class "Default")
      (node (ref "C112") (pin "1") (pinfunction "1_1") (pintype "passive"))
    )
    (net (code "69") (name "/PCIE_W_DISABLE2#") (class "Default")
      (node (ref "R76") (pin "1") (pinfunction "1_1") (pintype "passive"))
    )
    (net (code "70") (name "/R1_N") (class "Default")
      (node (ref "C125") (pin "2") (pinfunction "2_2") (pintype "passive"))
      (node (ref "IC6") (pin "R2") (pinfunction "SD1_RX_N_R2") (pintype "power_in"))
    )
    (net (code "71") (name "/R1_P") (class "Default")
      (node (ref "C118") (pin "2") (pinfunction "2_2") (pintype "passive"))
      (node (ref "IC6") (pin "P2") (pinfunction "SD1_RX_P_P2") (pintype "power_in"))
    )
    (net (code "72") (name "/T0_N") (class "Default")
      (node (ref "C116") (pin "2") (pinfunction "2_2") (pintype "passive"))
      (node (ref "IC6") (pin "R4") (pinfunction "SD1_TX_N_R4") (pintype "power_in"))
    )
    (net (code "73") (name "/T0_P") (class "Default")
      (node (ref "C114") (pin "2") (pinfunction "2_2") (pintype "passive"))
      (node (ref "IC6") (pin "P4") (pinfunction "SD1_TX_P_P4") (pintype "power_in"))
    )
    (net (code "74") (name "GND") (class "Default")
      (node (ref "C115") (pin "2") (pinfunction "2_2") (pintype "passive"))
      (node (ref "C117") (pin "2") (pinfunction "2_2") (pintype "passive"))
      (node (ref "C119") (pin "1") (pinfunction "1_1") (pintype "passive"))
      (node (ref "C120") (pin "1") (pinfunction "1_1") (pintype "passive"))
      (node (ref "C121") (pin "1") (pinfunction "1_1") (pintype "passive"))
      (node (ref "C122") (pin "1") (pinfunction "1_1") (pintype "passive"))
      (node (ref "C123") (pin "1") (pinfunction "1_1") (pintype "passive"))
      (node (ref "C124") (pin "2") (pinfunction "2_2") (pintype "passive"))
      (node (ref "C127") (pin "1") (pinfunction "1_1") (pintype "passive"))
      (node (ref "C128") (pin "2") (pinfunction "2_2") (pintype "passive"))
      (node (ref "C129") (pin "2") (pinfunction "2_2") (pintype "passive"))
      (node (ref "C130") (pin "1") (pinfunction "1_1") (pintype "passive"))
      (node (ref "C131") (pin "1") (pinfunction "1_1") (pintype "passive"))
      (node (ref "C133") (pin "1") (pinfunction "1_1") (pintype "passive"))
      (node (ref "C134") (pin "2") (pinfunction "2_2") (pintype "passive"))
      (node (ref "C135") (pin "2") (pinfunction "2_2") (pintype "passive"))
      (node (ref "C136") (pin "1") (pinfunction "1_1") (pintype "passive"))
      (node (ref "C137") (pin "1") (pinfunction "1_1") (pintype "passive"))
      (node (ref "C138") (pin "1") (pinfunction "1_1") (pintype "passive"))
      (node (ref "C139") (pin "1") (pinfunction "1_1") (pintype "passive"))
      (node (ref "C140") (pin "1") (pinfunction "1_1") (pintype "passive"))
      (node (ref "C141") (pin "1") (pinfunction "1_1") (pintype "passive"))
      (node (ref "C142") (pin "1") (pinfunction "1_1") (pintype "passive"))
      (node (ref "C143") (pin "1") (pinfunction "1_1") (pintype "passive"))
      (node (ref "C144") (pin "2") (pinfunction "2_2") (pintype "passive"))
      (node (ref "C145") (pin "1") (pinfunction "1_1") (pintype "passive"))
      (node (ref "C146") (pin "1") (pinfunction "1_1") (pintype "passive"))
      (node (ref "C147") (pin "1") (pinfunction "1_1") (pintype "passive"))
      (node (ref "C148") (pin "2") (pinfunction "2_2") (pintype "passive"))
      (node (ref "C149") (pin "1") (pinfunction "1_1") (pintype "passive"))
      (node (ref "C150") (pin "2") (pinfunction "2_2") (pintype "passive"))
      (node (ref "C151") (pin "2") (pinfunction "2_2") (pintype "passive"))
      (node (ref "C152") (pin "1") (pinfunction "1_1") (pintype "passive"))
      (node (ref "C153") (pin "1") (pinfunction "1_1") (pintype "passive"))
      (node (ref "C154") (pin "1") (pinfunction "1_1") (pintype "passive"))
      (node (ref "C155") (pin "1") (pinfunction "1_1") (pintype "passive"))
      (node (ref "C156") (pin "2") (pinfunction "2_2") (pintype "passive"))
      (node (ref "C157") (pin "1") (pinfunction "1_1") (pintype "passive"))
      (node (ref "C158") (pin "1") (pinfunction "1_1") (pintype "passive"))
      (node (ref "C159") (pin "1") (pinfunction "1_1") (pintype "passive"))
      (node (ref "C160") (pin "1") (pinfunction "1_1") (pintype "passive"))
      (node (ref "C161") (pin "1") (pinfunction "1_1") (pintype "passive"))
      (node (ref "C162") (pin "1") (pinfunction "1_1") (pintype "passive"))
      (node (ref "IC6") (pin "B1") (pinfunction "AFE_GND01_B1") (pintype "power_in"))
      (node (ref "IC6") (pin "B11") (pinfunction "AFE_GND04_B11") (pintype "power_in"))
      (node (ref "IC6") (pin "B13") (pinfunction "AFE_GND05_B13") (pintype "power_in"))
      (node (ref "IC6") (pin "B15") (pinfunction "AFE_GND06_B15") (pintype "power_in"))
      (node (ref "IC6") (pin "B3") (pinfunction "AFE_GND02_B3") (pintype "power_in"))
      (node (ref "IC6") (pin "B5") (pinfunction "AFE_GND03_B5") (pintype "power_in"))
      (node (ref "IC6") (pin "C10") (pinfunction "AFE_GND12_C10") (pintype "power_in"))
      (node (ref "IC6") (pin "C12") (pinfunction "AFE_GND13_C12") (pintype "power_in"))
      (node (ref "IC6") (pin "C14") (pinfunction "AFE_GND14_C14") (pintype "power_in"))
      (node (ref "IC6") (pin "C2") (pinfunction "AFE_GND07_C2") (pintype "power_in"))
      (node (ref "IC6") (pin "C4") (pinfunction "AFE_GND08_C4") (pintype "power_in"))
      (node (ref "IC6") (pin "C6") (pinfunction "AFE_GND09_C6") (pintype "power_in"))
      (node (ref "IC6") (pin "C7") (pinfunction "AFE_GND10_C7") (pintype "power_in"))
      (node (ref "IC6") (pin "C9") (pinfunction "AFE_GND11_C9") (pintype "power_in"))
      (node (ref "IC6") (pin "D10") (pinfunction "AFE_GND17_D10") (pintype "power_in"))
      (node (ref "IC6") (pin "D14") (pinfunction "AFE_GND18_D14") (pintype "power_in"))
      (node (ref "IC6") (pin "D2") (pinfunction "AFE_GND15_D2") (pintype "power_in"))
      (node (ref "IC6") (pin "D5") (pinfunction "VREF_RX_N_D5") (pintype "power_in"))
      (node (ref "IC6") (pin "D6") (pinfunction "AFE_GND16_D6") (pintype "power_in"))
      (node (ref "IC6") (pin "E1") (pinfunction "AFE_GND19_E1") (pintype "power_in"))
      (node (ref "IC6") (pin "E12") (pinfunction "AFE_GND23_E12") (pintype "power_in"))
      (node (ref "IC6") (pin "E15") (pinfunction "AFE_GND24_E15") (pintype "power_in"))
      (node (ref "IC6") (pin "E4") (pinfunction "AFE_GND20_E4") (pintype "power_in"))
      (node (ref "IC6") (pin "E7") (pinfunction "AFE_GND21_E7") (pintype "power_in"))
      (node (ref "IC6") (pin "E9") (pinfunction "AFE_GND22_E9") (pintype "power_in"))
      (node (ref "IC6") (pin "F12") (pinfunction "GND01_F12") (pintype "power_in"))
      (node (ref "IC6") (pin "F3") (pinfunction "AFE_GND25_F3") (pintype "power_in"))
      (node (ref "IC6") (pin "F4") (pinfunction "AFE_GND26_F4") (pintype "power_in"))
      (node (ref "IC6") (pin "F8") (pinfunction "AFE_GND27_F8") (pintype "power_in"))
      (node (ref "IC6") (pin "G11") (pinfunction "GND06_G11") (pintype "power_in"))
      (node (ref "IC6") (pin "G2") (pinfunction "AFE_GND28_G2") (pintype "power_in"))
      (node (ref "IC6") (pin "G3") (pinfunction "GND02_G3") (pintype "power_in"))
      (node (ref "IC6") (pin "G5") (pinfunction "GND03_G5") (pintype "power_in"))
      (node (ref "IC6") (pin "G7") (pinfunction "GND04_G7") (pintype "power_in"))
      (node (ref "IC6") (pin "G9") (pinfunction "GND05_G9") (pintype "power_in"))
      (node (ref "IC6") (pin "H1") (pinfunction "TD1_ANODE_H1") (pintype "power_in"))
      (node (ref "IC6") (pin "H12") (pinfunction "GND08_H12") (pintype "power_in"))
      (node (ref "IC6") (pin "H13") (pinfunction "LLCP_STIN_P_H13") (pintype "power_in"))
      (node (ref "IC6") (pin "H14") (pinfunction "LLCP_DIN_N_H14") (pintype "power_in"))
      (node (ref "IC6") (pin "H15") (pinfunction "LLCP_DIN_P_H15") (pintype "power_in"))
      (node (ref "IC6") (pin "H2") (pinfunction "TD1_CATHODE_H2") (pintype "power_in"))
      (node (ref "IC6") (pin "H8") (pinfunction "GND07_H8") (pintype "power_in"))
      (node (ref "IC6") (pin "J11") (pinfunction "GND14_J11") (pintype "power_in"))
      (node (ref "IC6") (pin "J13") (pinfunction "LLCP_STIN_N_J13") (pintype "power_in"))
      (node (ref "IC6") (pin "J2") (pinfunction "GND09_J2") (pintype "power_in"))
      (node (ref "IC6") (pin "J3") (pinfunction "GND10_J3") (pintype "power_in"))
      (node (ref "IC6") (pin "J5") (pinfunction "GND11_J5") (pintype "power_in"))
      (node (ref "IC6") (pin "J7") (pinfunction "GND12_J7") (pintype "power_in"))
      (node (ref "IC6") (pin "J9") (pinfunction "GND13_J9") (pintype "power_in"))
      (node (ref "IC6") (pin "K12") (pinfunction "GND16_K12") (pintype "power_in"))
      (node (ref "IC6") (pin "K2") (pinfunction "PROG_VDD_K2") (pintype "power_in"))
      (node (ref "IC6") (pin "K8") (pinfunction "GND15_K8") (pintype "power_in"))
      (node (ref "IC6") (pin "L1") (pinfunction "SD_GND1_L1") (pintype "power_in"))
      (node (ref "IC6") (pin "L11") (pinfunction "GND18_L11") (pintype "power_in"))
      (node (ref "IC6") (pin "L6") (pinfunction "SD_GND2_L6") (pintype "power_in"))
      (node (ref "IC6") (pin "L7") (pinfunction "SD_GND3_L7") (pintype "power_in"))
      (node (ref "IC6") (pin "L9") (pinfunction "GND17_L9") (pintype "power_in"))
      (node (ref "IC6") (pin "M2") (pinfunction "SD_GND4_M2") (pintype "power_in"))
      (node (ref "IC6") (pin "N2") (pinfunction "SD_GND5_N2") (pintype "power_in"))
      (node (ref "IC6") (pin "N4") (pinfunction "SD_GND6_N4") (pintype "power_in"))
      (node (ref "IC6") (pin "N6") (pinfunction "SD_GND7_N6") (pintype "power_in"))
      (node (ref "IC6") (pin "P1") (pinfunction "SD_GND8_P1") (pintype "power_in"))
      (node (ref "IC6") (pin "P3") (pinfunction "SD_GND9_P3") (pintype "power_in"))
      (node (ref "IC6") (pin "P5") (pinfunction "SD_GND10_P5") (pintype "power_in"))
      (node (ref "IC7") (pin "2") (pinfunction "GND_2") (pintype "passive"))
      (node (ref "J1") (pin "3") (pinfunction "3_3") (pintype "passive"))
      (node (ref "J1") (pin "5") (pinfunction "5_5") (pintype "passive"))
      (node (ref "J1") (pin "9") (pinfunction "9_9") (pintype "passive"))
      (node (ref "R104") (pin "2") (pinfunction "2_2") (pintype "passive"))
      (node (ref "R105") (pin "2") (pinfunction "2_2") (pintype "passive"))
      (node (ref "R106") (pin "2") (pinfunction "2_2") (pintype "passive"))
      (node (ref "R107") (pin "2") (pinfunction "2_2") (pintype "passive"))
      (node (ref "R108") (pin "2") (pinfunction "2_2") (pintype "passive"))
      (node (ref "R109") (pin "2") (pinfunction "2_2") (pintype "passive"))
      (node (ref "R110") (pin "2") (pinfunction "2_2") (pintype "passive"))
      (node (ref "R111") (pin "2") (pinfunction "2_2") (pintype "passive"))
      (node (ref "R112") (pin "2") (pinfunction "2_2") (pintype "passive"))
      (node (ref "R77") (pin "1") (pinfunction "1_1") (pintype "passive"))
      (node (ref "R85") (pin "2") (pinfunction "2_2") (pintype "passive"))
      (node (ref "R88") (pin "1") (pinfunction "1_1") (pintype "passive"))
      (node (ref "X7") (pin "1") (pinfunction "1_1") (pintype "passive"))
      (node (ref "X7") (pin "12") (pinfunction "12_12") (pintype "passive"))
      (node (ref "X7") (pin "15") (pinfunction "15_15") (pintype "passive"))
      (node (ref "X7") (pin "4") (pinfunction "4_4") (pintype "passive"))
      (node (ref "X7") (pin "7") (pinfunction "7_7") (pintype "passive"))
      (node (ref "X7") (pin "9") (pinfunction "9_9") (pintype "passive"))
      (node (ref "X7") (pin "MP1") (pinfunction "MP1_MP1") (pintype "passive"))
      (node (ref "X7") (pin "MP2") (pinfunction "MP2_MP2") (pintype "passive"))
    )
    (net (code "75") (name "Net-(C126-Pad1)") (class "Default")
      (node (ref "C126") (pin "1") (pinfunction "1_1") (pintype "passive"))
      (node (ref "R82") (pin "1") (pinfunction "1_1") (pintype "passive"))
    )
    (net (code "76") (name "Net-(C132-Pad1)") (class "Default")
      (node (ref "C132") (pin "1") (pinfunction "1_1") (pintype "passive"))
      (node (ref "R86") (pin "1") (pinfunction "1_1") (pintype "passive"))
    )
    (net (code "77") (name "Net-(IC6A-CLKOUT)") (class "Default")
      (node (ref "IC6") (pin "N13") (pinfunction "CLKOUT_N13") (pintype "power_in"))
      (node (ref "R79") (pin "2") (pinfunction "2_2") (pintype "passive"))
    )
    (net (code "78") (name "Net-(IC6A-GPIO_19_{slash}ASLEEP)") (class "Default")
      (node (ref "IC6") (pin "R12") (pinfunction "GPIO_19_/ASLEEP_R12") (pintype "power_in"))
      (node (ref "R76") (pin "2") (pinfunction "2_2") (pintype "passive"))
    )
    (net (code "79") (name "Net-(IC6A-SCAN_MODE_B)") (class "Default")
      (node (ref "IC6") (pin "M13") (pinfunction "SCAN_MODE_B_M13") (pintype "power_in"))
      (node (ref "R87") (pin "1") (pinfunction "1_1") (pintype "passive"))
    )
    (net (code "80") (name "Net-(IC6A-SD1_IMP_CAL_RX)") (class "Default")
      (node (ref "IC6") (pin "K4") (pinfunction "SD1_IMP_CAL_RX_K4") (pintype "power_in"))
      (node (ref "R81") (pin "1") (pinfunction "1_1") (pintype "passive"))
    )
    (net (code "81") (name "Net-(IC6A-SD1_IMP_CAL_TX)") (class "Default")
      (node (ref "IC6") (pin "M4") (pinfunction "SD1_IMP_CAL_TX_M4") (pintype "power_in"))
      (node (ref "R80") (pin "1") (pinfunction "1_1") (pintype "passive"))
    )
    (net (code "82") (name "Net-(IC6B-IREF_TX)") (class "Default")
      (node (ref "IC6") (pin "E8") (pinfunction "IREF_TX_E8") (pintype "power_in"))
      (node (ref "R104") (pin "1") (pinfunction "1_1") (pintype "passive"))
    )
    (net (code "83") (name "Net-(IC7-D)") (class "Default")
      (node (ref "IC7") (pin "5") (pinfunction "D_5") (pintype "passive"))
      (node (ref "R78") (pin "1") (pinfunction "1_1") (pintype "passive"))
      (node (ref "R84") (pin "2") (pinfunction "2_2") (pintype "passive"))
      (node (ref "R85") (pin "1") (pinfunction "1_1") (pintype "passive"))
    )
    (net (code "84") (name "Net-(IC7-Y)") (class "Default")
      (node (ref "C126") (pin "2") (pinfunction "2_2") (pintype "passive"))
      (node (ref "IC7") (pin "4") (pinfunction "Y_4") (pintype "passive"))
      (node (ref "R77") (pin "2") (pinfunction "2_2") (pintype "passive"))
      (node (ref "R78") (pin "2") (pinfunction "2_2") (pintype "passive"))
    )
    (net (code "85") (name "Net-(IC7-Z)") (class "Default")
      (node (ref "C132") (pin "2") (pinfunction "2_2") (pintype "passive"))
      (node (ref "IC7") (pin "3") (pinfunction "Z_3") (pintype "passive"))
      (node (ref "R88") (pin "2") (pinfunction "2_2") (pintype "passive"))
    )
    (net (code "86") (name "Net-(J1-Pad1)") (class "Default")
      (node (ref "J1") (pin "1") (pinfunction "1_1") (pintype "passive"))
      (node (ref "R90") (pin "1") (pinfunction "1_1") (pintype "passive"))
    )
    (net (code "87") (name "Net-(J1-Pad2)") (class "Default")
      (node (ref "J1") (pin "2") (pinfunction "2_2") (pintype "passive"))
      (node (ref "R91") (pin "2") (pinfunction "2_2") (pintype "passive"))
    )
    (net (code "88") (name "Net-(J1-Pad4)") (class "Default")
      (node (ref "J1") (pin "4") (pinfunction "4_4") (pintype "passive"))
      (node (ref "R92") (pin "2") (pinfunction "2_2") (pintype "passive"))
    )
    (net (code "89") (name "Net-(J1-Pad6)") (class "Default")
      (node (ref "J1") (pin "6") (pinfunction "6_6") (pintype "passive"))
      (node (ref "R93") (pin "2") (pinfunction "2_2") (pintype "passive"))
    )
    (net (code "90") (name "Net-(J1-Pad8)") (class "Default")
      (node (ref "J1") (pin "8") (pinfunction "8_8") (pintype "passive"))
      (node (ref "R94") (pin "2") (pinfunction "2_2") (pintype "passive"))
    )
    (net (code "91") (name "Net-(J1-Pad10)") (class "Default")
      (node (ref "J1") (pin "10") (pinfunction "10_10") (pintype "passive"))
      (node (ref "R95") (pin "1") (pinfunction "1_1") (pintype "passive"))
    )
    (net (code "92") (name "Net-(R79-Pad1)") (class "Default")
      (node (ref "R79") (pin "1") (pinfunction "1_1") (pintype "passive"))
      (node (ref "TP1") (pin "1") (pintype "passive"))
    )
    (net (code "93") (name "VCC0P9") (class "Default")
      (node (ref "C139") (pin "2") (pinfunction "2_2") (pintype "passive"))
      (node (ref "C140") (pin "2") (pinfunction "2_2") (pintype "passive"))
      (node (ref "C141") (pin "2") (pinfunction "2_2") (pintype "passive"))
      (node (ref "C142") (pin "2") (pinfunction "2_2") (pintype "passive"))
      (node (ref "C143") (pin "2") (pinfunction "2_2") (pintype "passive"))
      (node (ref "C144") (pin "1") (pinfunction "1_1") (pintype "passive"))
      (node (ref "C148") (pin "1") (pinfunction "1_1") (pintype "passive"))
      (node (ref "C156") (pin "1") (pinfunction "1_1") (pintype "passive"))
      (node (ref "IC6") (pin "G10") (pinfunction "VDD2_G10") (pintype "power_in"))
      (node (ref "IC6") (pin "G6") (pinfunction "VDD1_G6") (pintype "power_in"))
      (node (ref "IC6") (pin "H11") (pinfunction "VDD6_H11") (pintype "power_in"))
      (node (ref "IC6") (pin "H5") (pinfunction "VDD3_H5") (pintype "power_in"))
      (node (ref "IC6") (pin "H7") (pinfunction "VDD4_H7") (pintype "power_in"))
      (node (ref "IC6") (pin "H9") (pinfunction "VDD5_H9") (pintype "power_in"))
      (node (ref "IC6") (pin "J10") (pinfunction "VDD8_J10") (pintype "power_in"))
      (node (ref "IC6") (pin "J6") (pinfunction "VDD7_J6") (pintype "power_in"))
    )
    (net (code "94") (name "VCC0P9_AFE_CVDD") (class "Default")
      (node (ref "C148") (pin "3") (pinfunction "3_3") (pintype "passive"))
      (node (ref "C152") (pin "2") (pinfunction "2_2") (pintype "passive"))
      (node (ref "C153") (pin "2") (pinfunction "2_2") (pintype "passive"))
      (node (ref "C154") (pin "2") (pinfunction "2_2") (pintype "passive"))
      (node (ref "C155") (pin "2") (pinfunction "2_2") (pintype "passive"))
      (node (ref "IC6") (pin "F11") (pinfunction "AFE_CVDD2_F11") (pintype "power_in"))
      (node (ref "IC6") (pin "F5") (pinfunction "AFE_CVDD1_F5") (pintype "power_in"))
    )
    (net (code "95") (name "VCC0P9_AFE_SVDD") (class "Default")
      (node (ref "C149") (pin "2") (pinfunction "2_2") (pintype "passive"))
      (node (ref "C150") (pin "1") (pinfunction "1_1") (pintype "passive"))
      (node (ref "C151") (pin "1") (pinfunction "1_1") (pintype "passive"))
      (node (ref "C156") (pin "3") (pinfunction "3_3") (pintype "passive"))
      (node (ref "C157") (pin "2") (pinfunction "2_2") (pintype "passive"))
      (node (ref "C158") (pin "2") (pinfunction "2_2") (pintype "passive"))
      (node (ref "C159") (pin "2") (pinfunction "2_2") (pintype "passive"))
      (node (ref "C160") (pin "2") (pinfunction "2_2") (pintype "passive"))
      (node (ref "C161") (pin "2") (pinfunction "2_2") (pintype "passive"))
      (node (ref "C162") (pin "2") (pinfunction "2_2") (pintype "passive"))
      (node (ref "IC6") (pin "D3") (pinfunction "VREF_RX_P_D3") (pintype "power_in"))
      (node (ref "IC6") (pin "E10") (pinfunction "AFE_SVDD2_E10") (pintype "power_in"))
      (node (ref "IC6") (pin "E6") (pinfunction "AFE_SVDD1_E6") (pintype "power_in"))
      (node (ref "IC6") (pin "F7") (pinfunction "AFE_SVDD3_F7") (pintype "power_in"))
      (node (ref "IC6") (pin "F9") (pinfunction "AFE_SVDD4_F9") (pintype "power_in"))
    )
    (net (code "96") (name "VCC0P9_SD_SVDD") (class "Default")
      (node (ref "C144") (pin "3") (pinfunction "3_3") (pintype "passive"))
      (node (ref "C145") (pin "2") (pinfunction "2_2") (pintype "passive"))
      (node (ref "C146") (pin "2") (pinfunction "2_2") (pintype "passive"))
      (node (ref "C147") (pin "2") (pinfunction "2_2") (pintype "passive"))
      (node (ref "IC6") (pin "K5") (pinfunction "SD_SVDD1_K5") (pintype "power_in"))
      (node (ref "IC6") (pin "K7") (pinfunction "SD_SVDD2_K7") (pintype "power_in"))
      (node (ref "R81") (pin "2") (pinfunction "2_2") (pintype "passive"))
    )
    (net (code "97") (name "VCC1P8") (class "Default")
      (node (ref "C130") (pin "2") (pinfunction "2_2") (pintype "passive"))
      (node (ref "C131") (pin "2") (pinfunction "2_2") (pintype "passive"))
      (node (ref "C135") (pin "1") (pinfunction "1_1") (pintype "passive"))
      (node (ref "IC6") (pin "K1") (pinfunction "TH_VDD_K1") (pintype "power_in"))
      (node (ref "IC6") (pin "K11") (pinfunction "OVDD2_K11") (pintype "power_in"))
      (node (ref "IC6") (pin "K9") (pinfunction "OVDD1_K9") (pintype "power_in"))
      (node (ref "IC6") (pin "L10") (pinfunction "OVDD3_L10") (pintype "power_in"))
      (node (ref "R72") (pin "1") (pinfunction "1_1") (pintype "passive"))
      (node (ref "R73") (pin "1") (pinfunction "1_1") (pintype "passive"))
      (node (ref "R83") (pin "2") (pinfunction "2_2") (pintype "passive"))
      (node (ref "R87") (pin "2") (pinfunction "2_2") (pintype "passive"))
      (node (ref "R89") (pin "1") (pinfunction "1_1") (pintype "passive"))
      (node (ref "R90") (pin "2") (pinfunction "2_2") (pintype "passive"))
    )
    (net (code "98") (name "VCC1P8_AFE_OTVDD") (class "Default")
      (node (ref "C135") (pin "3") (pinfunction "3_3") (pintype "passive"))
      (node (ref "C136") (pin "2") (pinfunction "2_2") (pintype "passive"))
      (node (ref "C137") (pin "2") (pinfunction "2_2") (pintype "passive"))
      (node (ref "C138") (pin "2") (pinfunction "2_2") (pintype "passive"))
      (node (ref "IC6") (pin "C8") (pinfunction "AFE_OTVDD_C8") (pintype "power_in"))
      (node (ref "IC6") (pin "D11") (pinfunction "AFE_OMVDD_D11") (pintype "power_in"))
    )
    (net (code "99") (name "VCC1P8_AVDD_PLAT") (class "Default")
      (node (ref "C127") (pin "2") (pinfunction "2_2") (pintype "passive"))
      (node (ref "C128") (pin "1") (pinfunction "1_1") (pintype "passive"))
      (node (ref "C129") (pin "1") (pinfunction "1_1") (pintype "passive"))
      (node (ref "IC6") (pin "H3") (pinfunction "AVDD_PLAT_H3") (pintype "power_in"))
      (node (ref "R83") (pin "1") (pinfunction "1_1") (pintype "passive"))
    )
    (net (code "100") (name "VCC1P35") (class "Default")
      (node (ref "C117") (pin "1") (pinfunction "1_1") (pintype "passive"))
      (node (ref "R75") (pin "2") (pinfunction "2_2") (pintype "passive"))
    )
    (net (code "101") (name "VCC1P35_AVDD_SD_PLL") (class "Default")
      (node (ref "C119") (pin "2") (pinfunction "2_2") (pintype "passive"))
      (node (ref "C120") (pin "2") (pinfunction "2_2") (pintype "passive"))
      (node (ref "C124") (pin "1") (pinfunction "1_1") (pintype "passive"))
      (node (ref "IC6") (pin "L3") (pinfunction "AVDD_SD_PLL_L3") (pintype "power_in"))
      (node (ref "R75") (pin "1") (pinfunction "1_1") (pintype "passive"))
    )
    (net (code "102") (name "VCC1P35_SD_XVDD") (class "Default")
      (node (ref "C117") (pin "3") (pinfunction "3_3") (pintype "passive"))
      (node (ref "C121") (pin "2") (pinfunction "2_2") (pintype "passive"))
      (node (ref "C122") (pin "2") (pinfunction "2_2") (pintype "passive"))
      (node (ref "C123") (pin "2") (pinfunction "2_2") (pintype "passive"))
      (node (ref "IC6") (pin "M5") (pinfunction "SD_XVDD1_M5") (pintype "power_in"))
      (node (ref "IC6") (pin "M6") (pinfunction "SD_XVDD2_M6") (pintype "power_in"))
      (node (ref "R80") (pin "2") (pinfunction "2_2") (pintype "passive"))
    )
    (net (code "103") (name "VCC3P3") (class "Default")
      (node (ref "X7") (pin "8") (pinfunction "8_8") (pintype "passive"))
    )
    (net (code "104") (name "VCC3P3_CLK") (class "Default")
      (node (ref "C133") (pin "2") (pinfunction "2_2") (pintype "passive"))
      (node (ref "C134") (pin "1") (pinfunction "1_1") (pintype "passive"))
      (node (ref "IC7") (pin "1") (pinfunction "VCC_1") (pintype "passive"))
    )
    (net (code "105") (name "VCC3P3_M.2") (class "Default")
      (node (ref "R74") (pin "1") (pinfunction "1_1") (pintype "passive"))
    )
    (net (code "106") (name "unconnected-(IC6B-LLCP_DOUT_N-PadG13)") (class "Default")
      (node (ref "IC6") (pin "G13") (pinfunction "LLCP_DOUT_N_G13") (pintype "power_in+no_connect"))
    )
    (net (code "107") (name "unconnected-(IC6B-LLCP_DOUT_P-PadF13)") (class "Default")
      (node (ref "IC6") (pin "F13") (pinfunction "LLCP_DOUT_P_F13") (pintype "power_in+no_connect"))
    )
    (net (code "108") (name "unconnected-(IC6B-LLCP_STOUT_N-PadF14)") (class "Default")
      (node (ref "IC6") (pin "F14") (pinfunction "LLCP_STOUT_N_F14") (pintype "power_in+no_connect"))
    )
    (net (code "109") (name "unconnected-(IC6B-LLCP_STOUT_P-PadF15)") (class "Default")
      (node (ref "IC6") (pin "F15") (pinfunction "LLCP_STOUT_P_F15") (pintype "power_in+no_connect"))
    )
    (net (code "110") (name "unconnected-(IC6B-TX_DET-PadD13)") (class "Default")
      (node (ref "IC6") (pin "D13") (pinfunction "TX_DET_D13") (pintype "power_in+no_connect"))
    )
    (net (code "111") (name "unconnected-(J1-Pad7)") (class "Default")
      (node (ref "J1") (pin "7") (pinfunction "7_7") (pintype "passive+no_connect"))
    )
  )
)
